# switches.net
KiCad netlist of a schematic drawn in Altium Designer
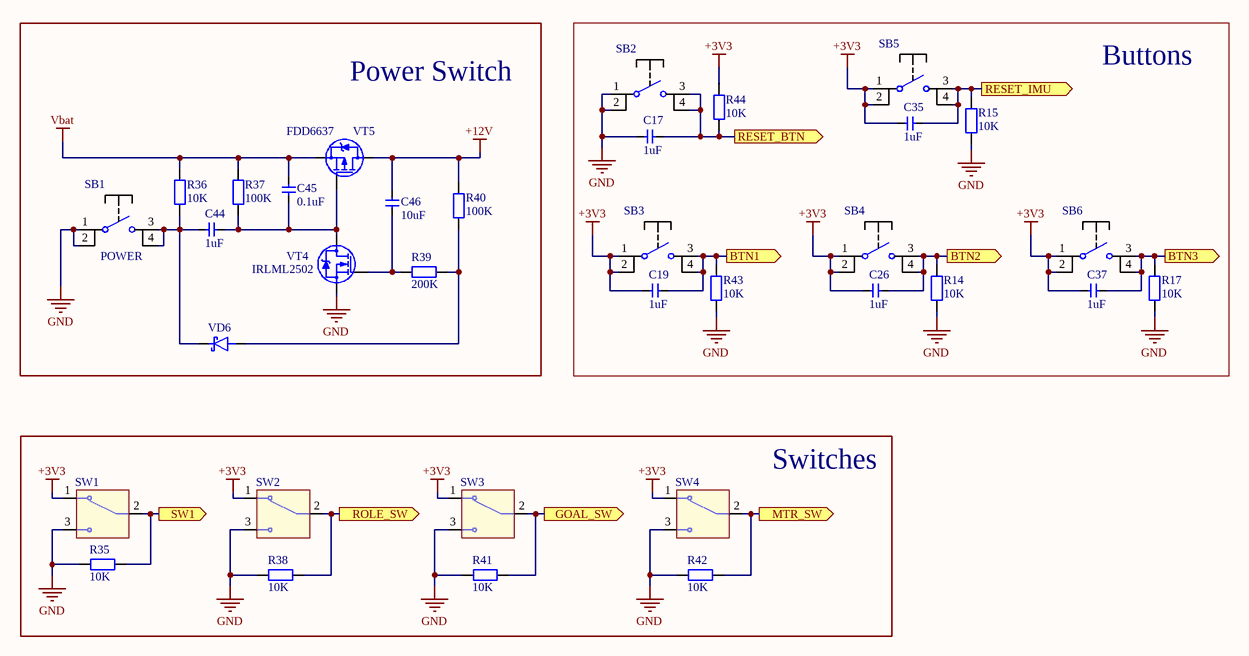
[diagram p0: switches.SchDoc]

(export (version "E")
  (design (tool "Eeschema 10.0.6"))
  (components
    (comp (ref "C17")
      (value "1uF")
      (footprint "CAP0805")
      (description "Ceramic SMD Cap")
      (libsource (lib "Asterisk") (part "CAP Ceramic"))
    )
    (comp (ref "C19")
      (value "1uF")
      (footprint "CAP0805")
      (description "Ceramic SMD Cap")
      (libsource (lib "Asterisk") (part "CAP Ceramic"))
    )
    (comp (ref "C26")
      (value "1uF")
      (footprint "CAP0805")
      (description "Ceramic SMD Cap")
      (libsource (lib "Asterisk") (part "CAP Ceramic"))
    )
    (comp (ref "C35")
      (value "1uF")
      (footprint "CAP0805")
      (description "Ceramic SMD Cap")
      (libsource (lib "Asterisk") (part "CAP Ceramic"))
    )
    (comp (ref "C37")
      (value "1uF")
      (footprint "CAP0805")
      (description "Ceramic SMD Cap")
      (libsource (lib "Asterisk") (part "CAP Ceramic"))
    )
    (comp (ref "C44")
      (value "1uF")
      (footprint "CAP0805")
      (description "Ceramic SMD Cap")
      (libsource (lib "Asterisk") (part "CAP Ceramic"))
    )
    (comp (ref "C45")
      (value "0.1uF")
      (footprint "CAP0805")
      (description "Ceramic SMD Cap")
      (libsource (lib "Asterisk") (part "CAP Ceramic"))
    )
    (comp (ref "C46")
      (value "10uF")
      (footprint "CAP0805")
      (description "Ceramic SMD Cap")
      (libsource (lib "Asterisk") (part "CAP Ceramic"))
    )
    (comp (ref "R14")
      (value "10K")
      (footprint "RES0805")
      (description "RES smd")
      (libsource (lib "Asterisk") (part "RES"))
    )
    (comp (ref "R15")
      (value "10K")
      (footprint "RES0805")
      (description "RES smd")
      (libsource (lib "Asterisk") (part "RES"))
    )
    (comp (ref "R17")
      (value "10K")
      (footprint "RES0805")
      (description "RES smd")
      (libsource (lib "Asterisk") (part "RES"))
    )
    (comp (ref "R35")
      (value "10K")
      (footprint "RES0805")
      (description "RES smd")
      (libsource (lib "Asterisk") (part "RES"))
    )
    (comp (ref "R36")
      (value "10K")
      (footprint "RES0805")
      (description "RES smd")
      (libsource (lib "Asterisk") (part "RES"))
    )
    (comp (ref "R37")
      (value "100K")
      (footprint "RES0805")
      (description "RES smd")
      (libsource (lib "Asterisk") (part "RES"))
    )
    (comp (ref "R38")
      (value "10K")
      (footprint "RES0805")
      (description "RES smd")
      (libsource (lib "Asterisk") (part "RES"))
    )
    (comp (ref "R39")
      (value "200K")
      (footprint "RES0805")
      (description "RES smd")
      (libsource (lib "Asterisk") (part "RES"))
    )
    (comp (ref "R40")
      (value "100K")
      (footprint "RES0805")
      (description "RES smd")
      (libsource (lib "Asterisk") (part "RES"))
    )
    (comp (ref "R41")
      (value "10K")
      (footprint "RES0805")
      (description "RES smd")
      (libsource (lib "Asterisk") (part "RES"))
    )
    (comp (ref "R42")
      (value "10K")
      (footprint "RES0805")
      (description "RES smd")
      (libsource (lib "Asterisk") (part "RES"))
    )
    (comp (ref "R43")
      (value "10K")
      (footprint "RES0805")
      (description "RES smd")
      (libsource (lib "Asterisk") (part "RES"))
    )
    (comp (ref "R44")
      (value "10K")
      (footprint "RES0805")
      (description "RES smd")
      (libsource (lib "Asterisk") (part "RES"))
    )
    (comp (ref "SB1")
      (value "POWER")
      (footprint "DTSM-61N-V-T/R")
      (description "Button")
      (libsource (lib "Asterisk") (part "Button"))
    )
    (comp (ref "SB2")
      (value "DTSM-61N-V-T/R")
      (footprint "DTSM-61N-V-T/R")
      (description "RESET")
      (libsource (lib "Asterisk") (part "Button"))
    )
    (comp (ref "SB3")
      (value "DTSM-61N-V-T/R")
      (footprint "DTSM-61N-V-T/R")
      (description "BTN1")
      (libsource (lib "Asterisk") (part "Button"))
    )
    (comp (ref "SB4")
      (value "DTSM-61N-V-T/R")
      (footprint "DTSM-61N-V-T/R")
      (description "BTN2")
      (libsource (lib "Asterisk") (part "Button"))
    )
    (comp (ref "SB5")
      (value "DTSM-61N-V-T/R")
      (footprint "DTSM-61N-V-T/R")
      (description "RESET_IMU")
      (libsource (lib "Asterisk") (part "Button"))
    )
    (comp (ref "SB6")
      (value "DTSM-61N-V-T/R")
      (footprint "DTSM-61N-V-T/R")
      (description "BTN3")
      (libsource (lib "Asterisk") (part "Button"))
    )
    (comp (ref "SW1")
      (value "ESP1010")
      (footprint "ESP1010")
      (description "SW1")
      (libsource (lib "Asterisk") (part "ESP1010"))
    )
    (comp (ref "SW2")
      (value "ESP1010")
      (footprint "ESP1010")
      (description "Role")
      (libsource (lib "Asterisk") (part "ESP1010"))
    )
    (comp (ref "SW3")
      (value "ESP1010")
      (footprint "ESP1010")
      (description "Goal")
      (libsource (lib "Asterisk") (part "ESP1010"))
    )
    (comp (ref "SW4")
      (value "ESP1010")
      (footprint "ESP1010")
      (description "Motor")
      (libsource (lib "Asterisk") (part "ESP1010"))
    )
    (comp (ref "VD6")
      (value "~")
      (footprint "DO-214AC (SMA)")
      (description "Diode Schottky")
      (libsource (lib "Asterisk") (part "Diode Schottky"))
    )
    (comp (ref "VT4")
      (value "IRLML2502")
      (footprint "SOT-23-3")
      (description "N-MOSFET\r\nUds = 20 V\r\nIds = 4.2 A\r\nRds = 0.035 Ohm\r\nP = 8 W")
      (libsource (lib "Asterisk") (part "IRLML2502"))
    )
    (comp (ref "VT5")
      (value "FDD6637")
      (footprint "DPAK")
      (description "P-MOSFET\r\nUds = 40 V\r\nIds = 40 A\r\nRds = 0.012 Ohm\r\nP = 3.0 W")
      (libsource (lib "Asterisk") (part "FDD6637"))
    )
  )
  (nets
    (net (code "1") (name "+3V3") (class "Default")
      (node (ref "C19") (pin "1") (pinfunction "1_1") (pintype "passive"))
      (node (ref "C26") (pin "1") (pinfunction "1_1") (pintype "passive"))
      (node (ref "C35") (pin "1") (pinfunction "1_1") (pintype "passive"))
      (node (ref "C37") (pin "1") (pinfunction "1_1") (pintype "passive"))
      (node (ref "R44") (pin "2") (pinfunction "2_2") (pintype "passive"))
      (node (ref "SB3") (pin "1") (pinfunction "1_1") (pintype "passive"))
      (node (ref "SB3") (pin "2") (pinfunction "2_2") (pintype "passive"))
      (node (ref "SB4") (pin "1") (pinfunction "1_1") (pintype "passive"))
      (node (ref "SB4") (pin "2") (pinfunction "2_2") (pintype "passive"))
      (node (ref "SB5") (pin "1") (pinfunction "1_1") (pintype "passive"))
      (node (ref "SB5") (pin "2") (pinfunction "2_2") (pintype "passive"))
      (node (ref "SB6") (pin "1") (pinfunction "1_1") (pintype "passive"))
      (node (ref "SB6") (pin "2") (pinfunction "2_2") (pintype "passive"))
      (node (ref "SW1") (pin "1") (pinfunction "1_1") (pintype "passive"))
      (node (ref "SW2") (pin "1") (pinfunction "1_1") (pintype "passive"))
      (node (ref "SW3") (pin "1") (pinfunction "1_1") (pintype "passive"))
      (node (ref "SW4") (pin "1") (pinfunction "1_1") (pintype "passive"))
    )
    (net (code "2") (name "+12V") (class "Default")
      (node (ref "C46") (pin "2") (pinfunction "2_2") (pintype "passive"))
      (node (ref "R40") (pin "2") (pinfunction "2_2") (pintype "passive"))
      (node (ref "VT5") (pin "D") (pinfunction "D_D") (pintype "passive"))
    )
    (net (code "3") (name "/BTN1") (class "Default")
      (node (ref "C19") (pin "2") (pinfunction "2_2") (pintype "passive"))
      (node (ref "R43") (pin "2") (pinfunction "2_2") (pintype "passive"))
      (node (ref "SB3") (pin "3") (pinfunction "3_3") (pintype "passive"))
      (node (ref "SB3") (pin "4") (pinfunction "4_4") (pintype "passive"))
    )
    (net (code "4") (name "/BTN2") (class "Default")
      (node (ref "C26") (pin "2") (pinfunction "2_2") (pintype "passive"))
      (node (ref "R14") (pin "2") (pinfunction "2_2") (pintype "passive"))
      (node (ref "SB4") (pin "3") (pinfunction "3_3") (pintype "passive"))
      (node (ref "SB4") (pin "4") (pinfunction "4_4") (pintype "passive"))
    )
    (net (code "5") (name "/BTN3") (class "Default")
      (node (ref "C37") (pin "2") (pinfunction "2_2") (pintype "passive"))
      (node (ref "R17") (pin "2") (pinfunction "2_2") (pintype "passive"))
      (node (ref "SB6") (pin "3") (pinfunction "3_3") (pintype "passive"))
      (node (ref "SB6") (pin "4") (pinfunction "4_4") (pintype "passive"))
    )
    (net (code "6") (name "/GOAL_SW") (class "Default")
      (node (ref "R41") (pin "2") (pinfunction "2_2") (pintype "passive"))
      (node (ref "SW3") (pin "2") (pinfunction "2_2") (pintype "passive"))
    )
    (net (code "7") (name "/MTR_SW") (class "Default")
      (node (ref "R42") (pin "2") (pinfunction "2_2") (pintype "passive"))
      (node (ref "SW4") (pin "2") (pinfunction "2_2") (pintype "passive"))
    )
    (net (code "8") (name "/RESET_BTN") (class "Default")
      (node (ref "C17") (pin "2") (pinfunction "2_2") (pintype "passive"))
      (node (ref "R44") (pin "1") (pinfunction "1_1") (pintype "passive"))
      (node (ref "SB2") (pin "3") (pinfunction "3_3") (pintype "passive"))
      (node (ref "SB2") (pin "4") (pinfunction "4_4") (pintype "passive"))
    )
    (net (code "9") (name "/RESET_IMU") (class "Default")
      (node (ref "C35") (pin "2") (pinfunction "2_2") (pintype "passive"))
      (node (ref "R15") (pin "2") (pinfunction "2_2") (pintype "passive"))
      (node (ref "SB5") (pin "3") (pinfunction "3_3") (pintype "passive"))
      (node (ref "SB5") (pin "4") (pinfunction "4_4") (pintype "passive"))
    )
    (net (code "10") (name "/ROLE_SW") (class "Default")
      (node (ref "R38") (pin "2") (pinfunction "2_2") (pintype "passive"))
      (node (ref "SW2") (pin "2") (pinfunction "2_2") (pintype "passive"))
    )
    (net (code "11") (name "/SW1") (class "Default")
      (node (ref "R35") (pin "2") (pinfunction "2_2") (pintype "passive"))
      (node (ref "SW1") (pin "2") (pinfunction "2_2") (pintype "passive"))
    )
    (net (code "12") (name "GND") (class "Default")
      (node (ref "C17") (pin "1") (pinfunction "1_1") (pintype "passive"))
      (node (ref "R14") (pin "1") (pinfunction "1_1") (pintype "passive"))
      (node (ref "R15") (pin "1") (pinfunction "1_1") (pintype "passive"))
      (node (ref "R17") (pin "1") (pinfunction "1_1") (pintype "passive"))
      (node (ref "R35") (pin "1") (pinfunction "1_1") (pintype "passive"))
      (node (ref "R38") (pin "1") (pinfunction "1_1") (pintype "passive"))
      (node (ref "R41") (pin "1") (pinfunction "1_1") (pintype "passive"))
      (node (ref "R42") (pin "1") (pinfunction "1_1") (pintype "passive"))
      (node (ref "R43") (pin "1") (pinfunction "1_1") (pintype "passive"))
      (node (ref "SB1") (pin "1") (pinfunction "1_1") (pintype "passive"))
      (node (ref "SB1") (pin "2") (pinfunction "2_2") (pintype "passive"))
      (node (ref "SB2") (pin "1") (pinfunction "1_1") (pintype "passive"))
      (node (ref "SB2") (pin "2") (pinfunction "2_2") (pintype "passive"))
      (node (ref "SW1") (pin "3") (pinfunction "3_3") (pintype "passive"))
      (node (ref "SW2") (pin "3") (pinfunction "3_3") (pintype "passive"))
      (node (ref "SW3") (pin "3") (pinfunction "3_3") (pintype "passive"))
      (node (ref "SW4") (pin "3") (pinfunction "3_3") (pintype "passive"))
      (node (ref "VT4") (pin "S") (pinfunction "S_S") (pintype "passive"))
    )
    (net (code "13") (name "Net-(C44-Pad1)") (class "Default")
      (node (ref "C44") (pin "1") (pinfunction "1_1") (pintype "passive"))
      (node (ref "C45") (pin "1") (pinfunction "1_1") (pintype "passive"))
      (node (ref "R37") (pin "2") (pinfunction "2_2") (pintype "passive"))
      (node (ref "VT4") (pin "D") (pinfunction "D_D") (pintype "passive"))
      (node (ref "VT5") (pin "G") (pinfunction "G_G") (pintype "passive"))
    )
    (net (code "14") (name "Net-(C44-Pad2)") (class "Default")
      (node (ref "C44") (pin "2") (pinfunction "2_2") (pintype "passive"))
      (node (ref "R36") (pin "2") (pinfunction "2_2") (pintype "passive"))
      (node (ref "SB1") (pin "3") (pinfunction "3_3") (pintype "passive"))
      (node (ref "SB1") (pin "4") (pinfunction "4_4") (pintype "passive"))
      (node (ref "VD6") (pin "K") (pinfunction "K_K") (pintype "passive"))
    )
    (net (code "15") (name "Net-(C46-Pad1)") (class "Default")
      (node (ref "C46") (pin "1") (pinfunction "1_1") (pintype "passive"))
      (node (ref "R39") (pin "2") (pinfunction "2_2") (pintype "passive"))
      (node (ref "VT4") (pin "G") (pinfunction "G_G") (pintype "passive"))
    )
    (net (code "16") (name "Net-(R39-Pad1)") (class "Default")
      (node (ref "R39") (pin "1") (pinfunction "1_1") (pintype "passive"))
      (node (ref "R40") (pin "1") (pinfunction "1_1") (pintype "passive"))
      (node (ref "VD6") (pin "A") (pinfunction "A_A") (pintype "passive"))
    )
    (net (code "17") (name "Vbat") (class "Default")
      (node (ref "C45") (pin "2") (pinfunction "2_2") (pintype "passive"))
      (node (ref "R36") (pin "1") (pinfunction "1_1") (pintype "passive"))
      (node (ref "R37") (pin "1") (pinfunction "1_1") (pintype "passive"))
      (node (ref "VT5") (pin "S") (pinfunction "S_S") (pintype "passive"))
    )
  )
)
